# LEDBoard.net
KiCad netlist of a schematic drawn in Altium Designer
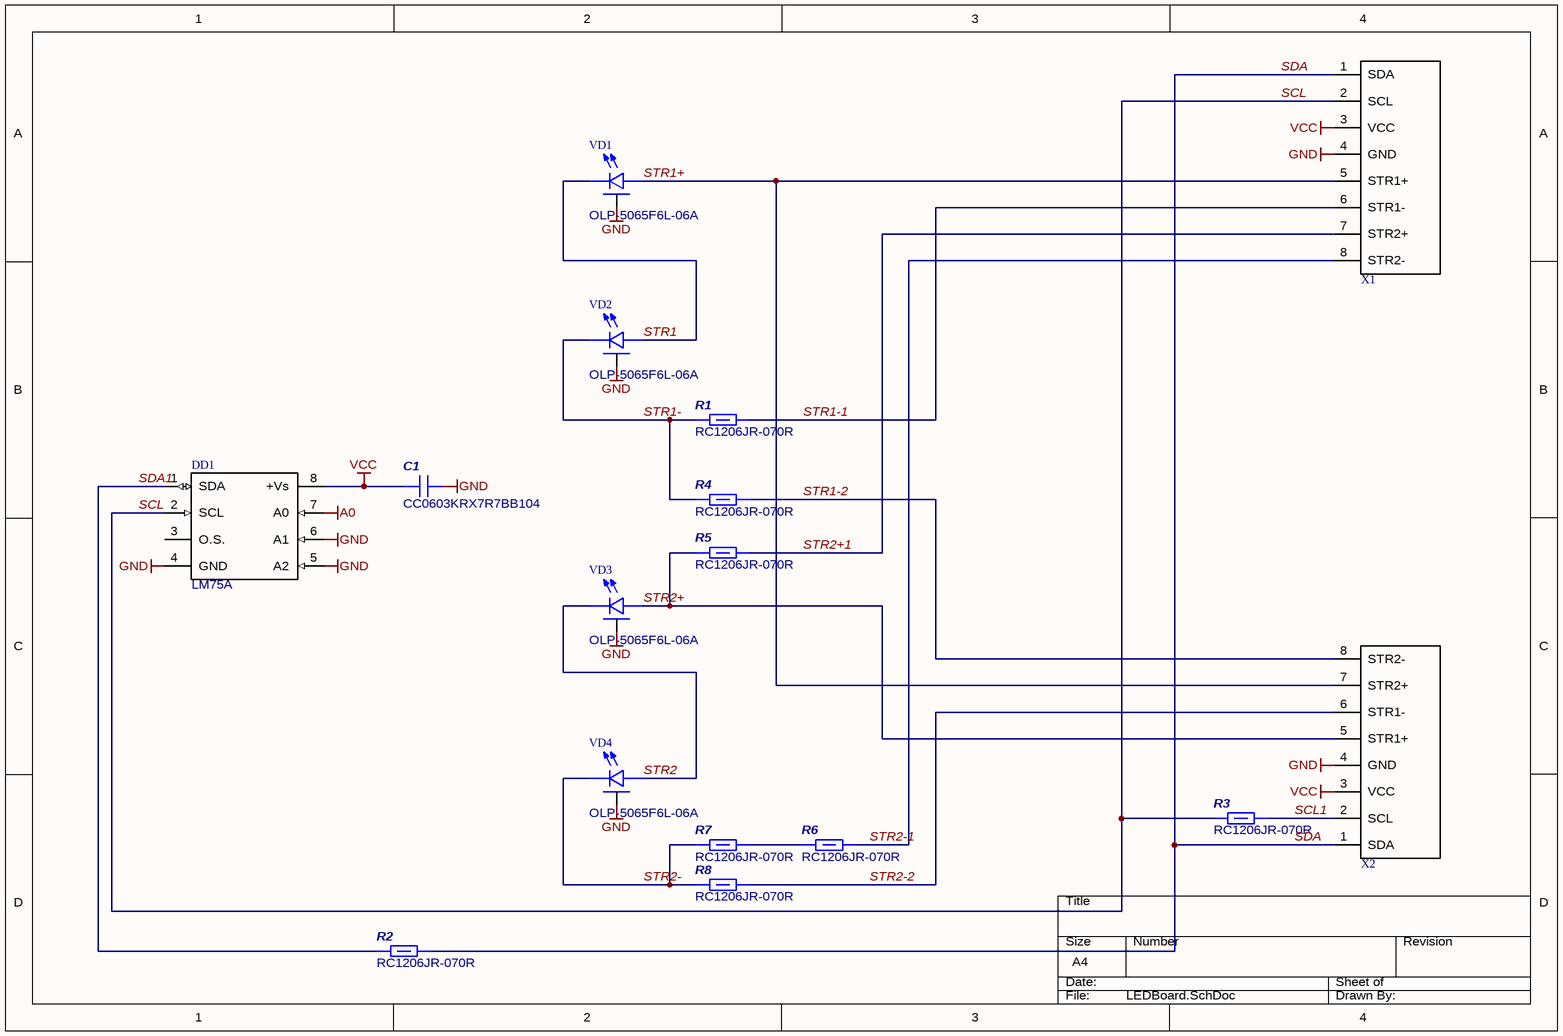
[diagram p0: LEDBoard.SchDoc]

(export (version "E")
  (design (tool "Eeschema 10.0.6"))
  (components
    (comp (ref "C1")
      (value "CC0603KRX7R7BB104")
      (footprint "CapacitorSMD0603(manual)")
      (description "CAPACITOR Capacitor SMD 0603 1.6x0.8mm")
      (libsource (lib "Integrated_Library") (part "CapacitorSMD0603(reflow)"))
    )
    (comp (ref "DD1")
      (value "LM75A")
      (footprint "SO8_FLIPPED")
      (description "IC Temperature sensor")
      (libsource (lib "Integrated_Library") (part "LM75A"))
    )
    (comp (ref "R1")
      (value "RC1206JR-070R")
      (footprint "ResistorSMD1206(manual)")
      (description "RESISTOR Resistor SMD 1210 3.1x1.6mm")
      (libsource (lib "Integrated_Library") (part "ResistorSMD1206"))
    )
    (comp (ref "R2")
      (value "RC1206JR-070R")
      (footprint "ResistorSMD1206(manual)")
      (description "RESISTOR Resistor SMD 1210 3.1x1.6mm")
      (libsource (lib "Integrated_Library") (part "ResistorSMD1206"))
    )
    (comp (ref "R3")
      (value "RC1206JR-070R")
      (footprint "ResistorSMD1206(manual)")
      (description "RESISTOR Resistor SMD 1210 3.1x1.6mm")
      (libsource (lib "Integrated_Library") (part "ResistorSMD1206"))
    )
    (comp (ref "R4")
      (value "RC1206JR-070R")
      (footprint "ResistorSMD1206(manual)")
      (description "RESISTOR Resistor SMD 1210 3.1x1.6mm")
      (libsource (lib "Integrated_Library") (part "ResistorSMD1206"))
    )
    (comp (ref "R5")
      (value "RC1206JR-070R")
      (footprint "ResistorSMD1206(manual)")
      (description "RESISTOR Resistor SMD 1210 3.1x1.6mm")
      (libsource (lib "Integrated_Library") (part "ResistorSMD1206"))
    )
    (comp (ref "R6")
      (value "RC1206JR-070R")
      (footprint "ResistorSMD1206(manual)")
      (description "RESISTOR Resistor SMD 1210 3.1x1.6mm")
      (libsource (lib "Integrated_Library") (part "ResistorSMD1206"))
    )
    (comp (ref "R7")
      (value "RC1206JR-070R")
      (footprint "ResistorSMD1206(manual)")
      (description "RESISTOR Resistor SMD 1210 3.1x1.6mm")
      (libsource (lib "Integrated_Library") (part "ResistorSMD1206"))
    )
    (comp (ref "R8")
      (value "RC1206JR-070R")
      (footprint "ResistorSMD1206(manual)")
      (description "RESISTOR Resistor SMD 1210 3.1x1.6mm")
      (libsource (lib "Integrated_Library") (part "ResistorSMD1206"))
    )
    (comp (ref "VD1")
      (value "OLP-5065F6L-06A")
      (footprint "OLP-5065F6L-06A(manualVar2)")
      (description "White LED 1.0W 155lm 3.0V 350mA")
      (libsource (lib "LED") (part "OLP-5065F6L-06A"))
    )
    (comp (ref "VD2")
      (value "OLP-5065F6L-06A")
      (footprint "OLP-5065F6L-06A(manualVar2)")
      (description "White LED 1.0W 155lm 3.0V 350mA")
      (libsource (lib "LED") (part "OLP-5065F6L-06A"))
    )
    (comp (ref "VD3")
      (value "OLP-5065F6L-06A")
      (footprint "OLP-5065F6L-06A(manualVar2)")
      (description "White LED 1.0W 155lm 3.0V 350mA")
      (libsource (lib "LED") (part "OLP-5065F6L-06A"))
    )
    (comp (ref "VD4")
      (value "OLP-5065F6L-06A")
      (footprint "OLP-5065F6L-06A(manualVar2)")
      (description "White LED 1.0W 155lm 3.0V 350mA")
      (libsource (lib "LED") (part "OLP-5065F6L-06A"))
    )
    (comp (ref "X1")
      (value "ConnectorLEDSide")
      (footprint "ConnectorLEDSide")
      (libsource (lib "MBLv1") (part "ConnectorLEDSide"))
    )
    (comp (ref "X2")
      (value "ConnectorLEDSide")
      (footprint "ConnectorLEDSide")
      (libsource (lib "") (part "ConnectorLEDSide_1"))
    )
  )
  (nets
    (net (code "1") (name "/SCL") (class "Default")
      (node (ref "DD1") (pin "2") (pinfunction "SCL_2") (pintype "input"))
      (node (ref "R3") (pin "1") (pinfunction "1_1") (pintype "passive"))
      (node (ref "X1") (pin "2") (pinfunction "SCL_2") (pintype "passive"))
    )
    (net (code "2") (name "/SCL1") (class "Default")
      (node (ref "R3") (pin "2") (pinfunction "2_2") (pintype "passive"))
      (node (ref "X2") (pin "2") (pinfunction "SCL_2") (pintype "passive"))
    )
    (net (code "3") (name "/SDA") (class "Default")
      (node (ref "R2") (pin "2") (pinfunction "2_2") (pintype "passive"))
      (node (ref "X1") (pin "1") (pinfunction "SDA_1") (pintype "passive"))
      (node (ref "X2") (pin "1") (pinfunction "SDA_1") (pintype "passive"))
    )
    (net (code "4") (name "/SDA1") (class "Default")
      (node (ref "DD1") (pin "1") (pinfunction "SDA_1") (pintype "bidirectional"))
      (node (ref "R2") (pin "1") (pinfunction "1_1") (pintype "passive"))
    )
    (net (code "5") (name "/STR1") (class "Default")
      (node (ref "VD1") (pin "1") (pintype "passive"))
      (node (ref "VD2") (pin "2") (pintype "passive"))
    )
    (net (code "6") (name "/STR1+") (class "Default")
      (node (ref "VD1") (pin "2") (pintype "passive"))
      (node (ref "X1") (pin "5") (pinfunction "STR1+_5") (pintype "passive"))
      (node (ref "X2") (pin "7") (pinfunction "STR2+_7") (pintype "passive"))
    )
    (net (code "7") (name "/STR1-") (class "Default")
      (node (ref "R1") (pin "1") (pinfunction "1_1") (pintype "passive"))
      (node (ref "R4") (pin "1") (pinfunction "1_1") (pintype "passive"))
      (node (ref "VD2") (pin "1") (pintype "passive"))
    )
    (net (code "8") (name "/STR1-1") (class "Default")
      (node (ref "R1") (pin "2") (pinfunction "2_2") (pintype "passive"))
      (node (ref "X1") (pin "6") (pinfunction "STR1-_6") (pintype "passive"))
    )
    (net (code "9") (name "/STR1-2") (class "Default")
      (node (ref "R4") (pin "2") (pinfunction "2_2") (pintype "passive"))
      (node (ref "X2") (pin "8") (pinfunction "STR2-_8") (pintype "passive"))
    )
    (net (code "10") (name "/STR2") (class "Default")
      (node (ref "VD3") (pin "1") (pintype "passive"))
      (node (ref "VD4") (pin "2") (pintype "passive"))
    )
    (net (code "11") (name "/STR2+") (class "Default")
      (node (ref "R5") (pin "1") (pinfunction "1_1") (pintype "passive"))
      (node (ref "VD3") (pin "2") (pintype "passive"))
      (node (ref "X2") (pin "5") (pinfunction "STR1+_5") (pintype "passive"))
    )
    (net (code "12") (name "/STR2+1") (class "Default")
      (node (ref "R5") (pin "2") (pinfunction "2_2") (pintype "passive"))
      (node (ref "X1") (pin "7") (pinfunction "STR2+_7") (pintype "passive"))
    )
    (net (code "13") (name "/STR2-") (class "Default")
      (node (ref "R7") (pin "1") (pinfunction "1_1") (pintype "passive"))
      (node (ref "R8") (pin "1") (pinfunction "1_1") (pintype "passive"))
      (node (ref "VD4") (pin "1") (pintype "passive"))
    )
    (net (code "14") (name "/STR2-1") (class "Default")
      (node (ref "R6") (pin "2") (pinfunction "2_2") (pintype "passive"))
      (node (ref "X1") (pin "8") (pinfunction "STR2-_8") (pintype "passive"))
    )
    (net (code "15") (name "/STR2-2") (class "Default")
      (node (ref "R8") (pin "2") (pinfunction "2_2") (pintype "passive"))
      (node (ref "X2") (pin "6") (pinfunction "STR1-_6") (pintype "passive"))
    )
    (net (code "16") (name "A0") (class "Default")
      (node (ref "DD1") (pin "7") (pinfunction "A0_7") (pintype "input"))
    )
    (net (code "17") (name "GND") (class "Default")
      (node (ref "C1") (pin "1") (pintype "passive"))
      (node (ref "DD1") (pin "4") (pinfunction "GND_4") (pintype "power_in"))
      (node (ref "DD1") (pin "5") (pinfunction "A2_5") (pintype "input"))
      (node (ref "DD1") (pin "6") (pinfunction "A1_6") (pintype "input"))
      (node (ref "VD1") (pin "3") (pintype "passive"))
      (node (ref "VD2") (pin "3") (pintype "passive"))
      (node (ref "VD3") (pin "3") (pintype "passive"))
      (node (ref "VD4") (pin "3") (pintype "passive"))
      (node (ref "X1") (pin "4") (pinfunction "GND_4") (pintype "passive"))
      (node (ref "X2") (pin "4") (pinfunction "GND_4") (pintype "passive"))
    )
    (net (code "18") (name "Net-(R6-Pad1)") (class "Default")
      (node (ref "R6") (pin "1") (pinfunction "1_1") (pintype "passive"))
      (node (ref "R7") (pin "2") (pinfunction "2_2") (pintype "passive"))
    )
    (net (code "19") (name "VCC") (class "Default")
      (node (ref "C1") (pin "2") (pintype "passive"))
      (node (ref "DD1") (pin "8") (pinfunction "+Vs_8") (pintype "power_in"))
      (node (ref "X1") (pin "3") (pinfunction "VCC_3") (pintype "passive"))
      (node (ref "X2") (pin "3") (pinfunction "VCC_3") (pintype "passive"))
    )
    (net (code "20") (name "unconnected-(DD1-O.S.-Pad3)") (class "Default")
      (node (ref "DD1") (pin "3") (pinfunction "O.S._3") (pintype "open_collector"))
    )
  )
)
